# Entrenadorv01.net
KiCad netlist of a schematic drawn in EAGLE
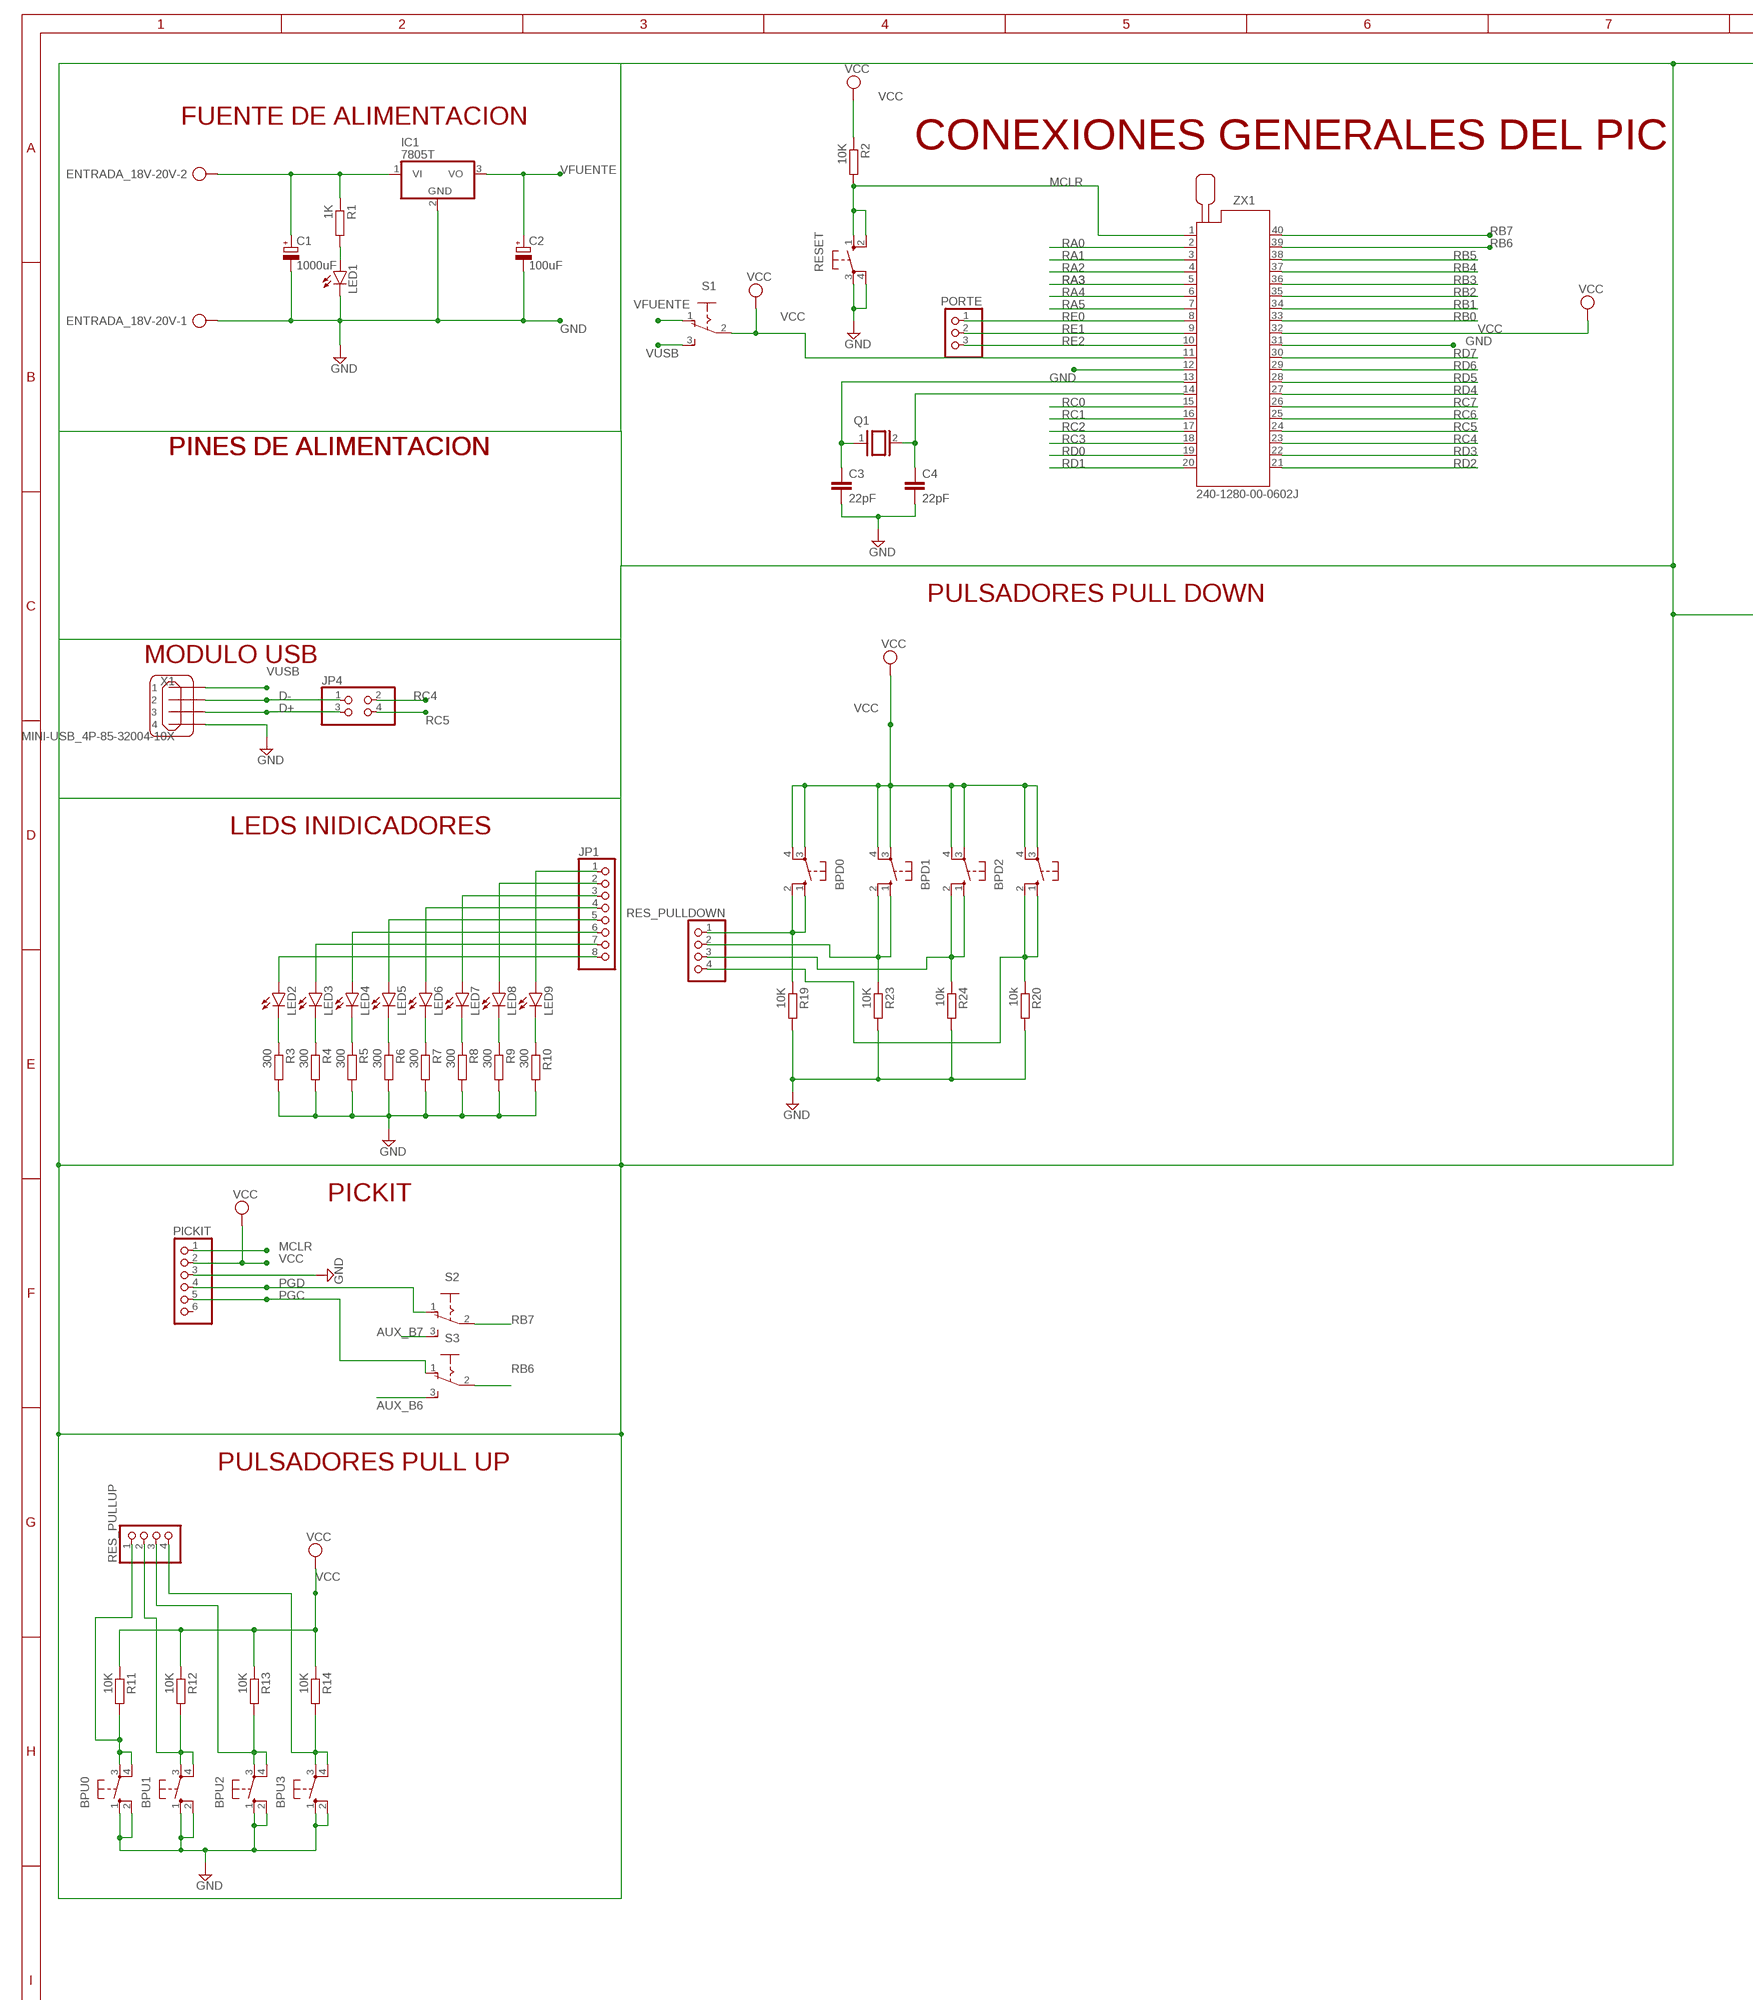
[diagram p0: schematic, sheet 1, part 1 of 2]
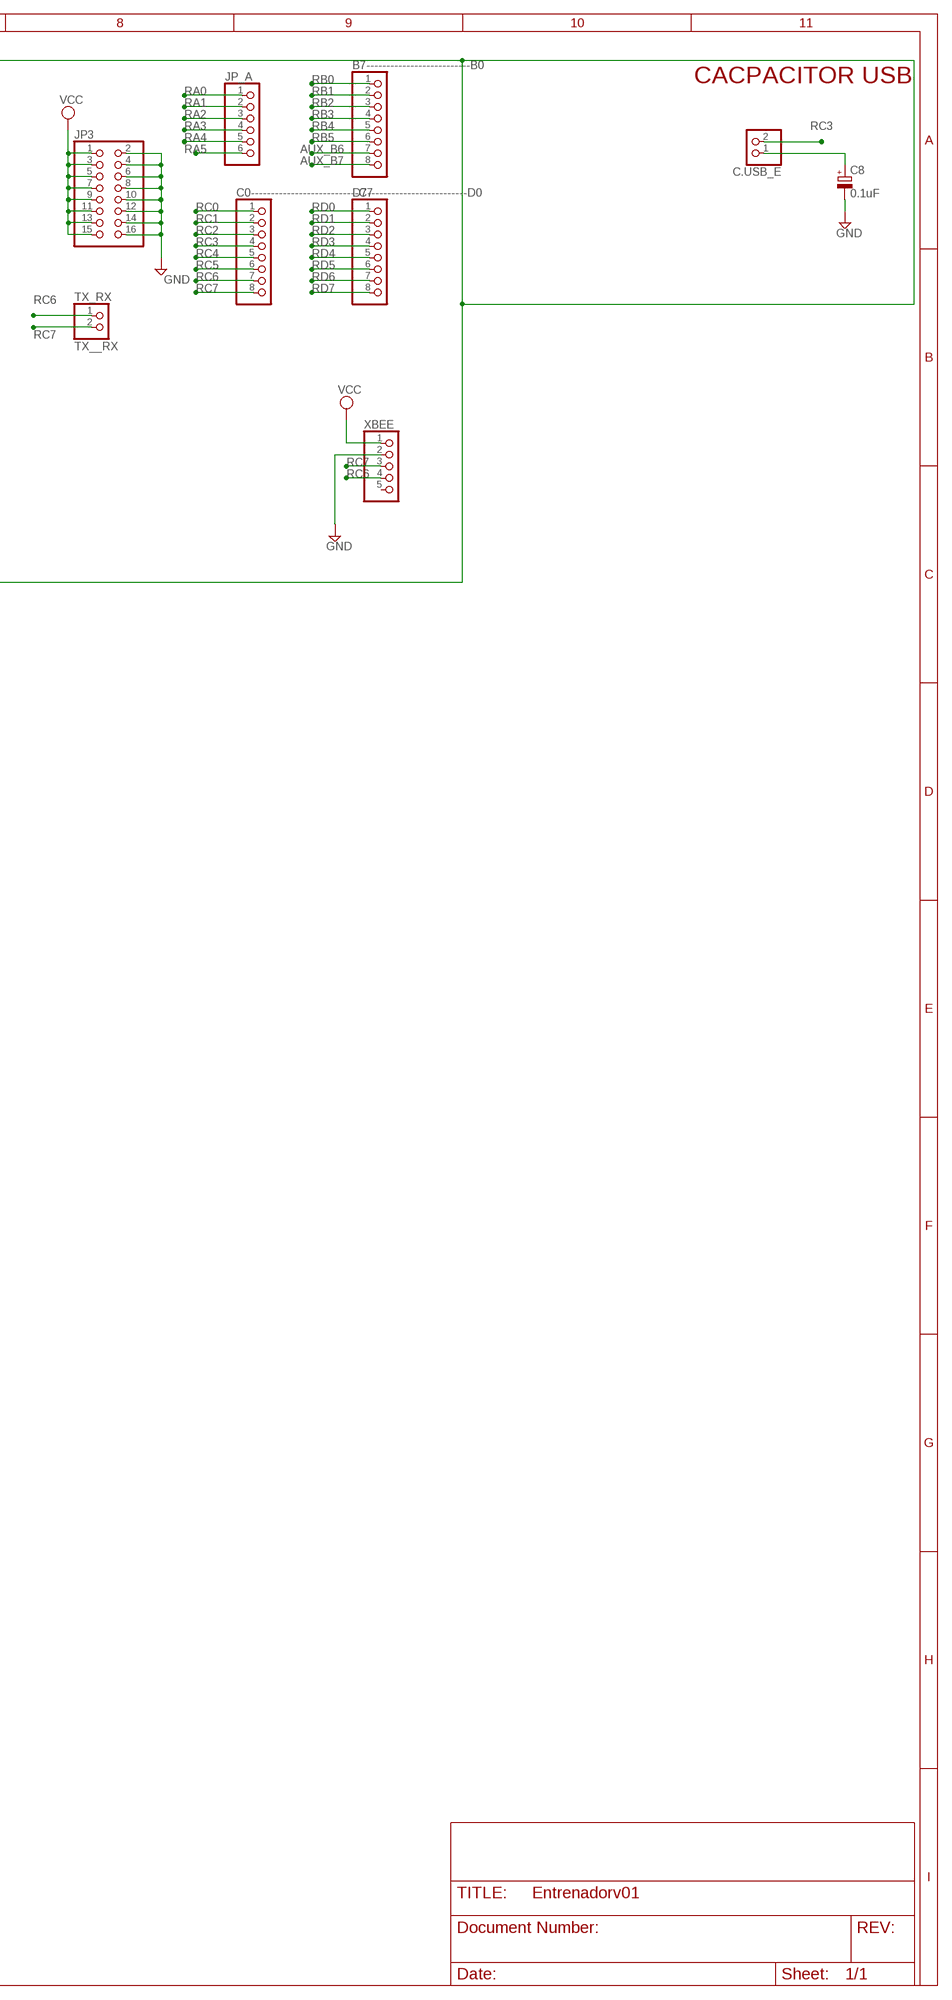
[diagram p1: schematic, sheet 1, part 2 of 2]

(export (version "E")
  (design (tool "Eeschema 10.0.6"))
  (components
    (comp (ref "B7--------------------------B0")
      (value "PINHD-1X8")
      (footprint "eagle-import:1X08")
      (libsource (lib "eagle-import") (part "PINHD-1X8"))
    )
    (comp (ref "BPD0")
      (value "10-XX")
      (footprint "eagle-import:B3F-10XX")
      (fields (field (name "MPN") "B3F-1000"))
      (libsource (lib "eagle-import") (part "10-XX"))
    )
    (comp (ref "BPD1")
      (value "10-XX")
      (footprint "eagle-import:B3F-10XX")
      (fields (field (name "MPN") "B3F-1000"))
      (libsource (lib "eagle-import") (part "10-XX"))
    )
    (comp (ref "BPD2")
      (value "10-XX")
      (footprint "eagle-import:B3F-10XX")
      (fields (field (name "MPN") "B3F-1000"))
      (libsource (lib "eagle-import") (part "10-XX"))
    )
    (comp (ref "BPD3")
      (value "10-XX")
      (footprint "eagle-import:B3F-10XX")
      (fields (field (name "MPN") "B3F-1000"))
      (libsource (lib "eagle-import") (part "10-XX"))
    )
    (comp (ref "BPU0")
      (value "10-XX")
      (footprint "eagle-import:B3F-10XX")
      (fields (field (name "MPN") "B3F-1000"))
      (libsource (lib "eagle-import") (part "10-XX"))
    )
    (comp (ref "BPU1")
      (value "10-XX")
      (footprint "eagle-import:B3F-10XX")
      (fields (field (name "MPN") "B3F-1000"))
      (libsource (lib "eagle-import") (part "10-XX"))
    )
    (comp (ref "BPU2")
      (value "10-XX")
      (footprint "eagle-import:B3F-10XX")
      (fields (field (name "MPN") "B3F-1000"))
      (libsource (lib "eagle-import") (part "10-XX"))
    )
    (comp (ref "BPU3")
      (value "10-XX")
      (footprint "eagle-import:B3F-10XX")
      (fields (field (name "MPN") "B3F-1000"))
      (libsource (lib "eagle-import") (part "10-XX"))
    )
    (comp (ref "C.USB_E")
      (value "PINHD-1X2")
      (footprint "eagle-import:1X02")
      (libsource (lib "eagle-import") (part "PINHD-1X2"))
    )
    (comp (ref "C0---------------------------C7")
      (value "PINHD-1X8")
      (footprint "eagle-import:1X08")
      (libsource (lib "eagle-import") (part "PINHD-1X8"))
    )
    (comp (ref "C1")
      (value "1000uF")
      (footprint "eagle-import:E5-10,5")
      (libsource (lib "eagle-import") (part "CPOL-EUE5-10.5"))
    )
    (comp (ref "C2")
      (value "100uF")
      (footprint "eagle-import:E5-10,5")
      (libsource (lib "eagle-import") (part "CPOL-EUE5-10.5"))
    )
    (comp (ref "C3")
      (value "22pF")
      (footprint "eagle-import:C025-025X050")
      (libsource (lib "eagle-import") (part "C-EU025-025X050"))
    )
    (comp (ref "C4")
      (value "22pF")
      (footprint "eagle-import:C025-025X050")
      (libsource (lib "eagle-import") (part "C-EU025-025X050"))
    )
    (comp (ref "C8")
      (value "0.1uF")
      (footprint "eagle-import:E1,8-4")
      (libsource (lib "eagle-import") (part "CPOL-EUE1.8-4"))
    )
    (comp (ref "D7-------------------------D0")
      (value "PINHD-1X8")
      (footprint "eagle-import:1X08")
      (libsource (lib "eagle-import") (part "PINHD-1X8"))
    )
    (comp (ref "ENTRADA_18V-20V")
      (value "AK300/2")
      (footprint "eagle-import:AK300_2")
      (libsource (lib "eagle-import") (part "AK300/2"))
    )
    (comp (ref "IC1")
      (value "7805T")
      (footprint "eagle-import:TO220H")
      (libsource (lib "eagle-import") (part "78T05"))
    )
    (comp (ref "JP1")
      (value "PINHD-1X8")
      (footprint "eagle-import:1X08")
      (libsource (lib "eagle-import") (part "PINHD-1X8"))
    )
    (comp (ref "JP3")
      (value "PINHD-2X8")
      (footprint "eagle-import:2X08")
      (libsource (lib "eagle-import") (part "PINHD-2X8"))
    )
    (comp (ref "JP4")
      (value "PINHD-2X2")
      (footprint "eagle-import:2X02")
      (libsource (lib "eagle-import") (part "PINHD-2X2"))
    )
    (comp (ref "JP_A")
      (value "PINHD-1X6")
      (footprint "eagle-import:1X06")
      (libsource (lib "eagle-import") (part "PINHD-1X6"))
    )
    (comp (ref "LED1")
      (value "LED3MM")
      (footprint "eagle-import:LED3MM")
      (libsource (lib "eagle-import") (part "LED3MM"))
    )
    (comp (ref "LED2")
      (value "LED3MM")
      (footprint "eagle-import:LED3MM")
      (libsource (lib "eagle-import") (part "LED3MM"))
    )
    (comp (ref "LED3")
      (value "LED3MM")
      (footprint "eagle-import:LED3MM")
      (libsource (lib "eagle-import") (part "LED3MM"))
    )
    (comp (ref "LED4")
      (value "LED3MM")
      (footprint "eagle-import:LED3MM")
      (libsource (lib "eagle-import") (part "LED3MM"))
    )
    (comp (ref "LED5")
      (value "LED3MM")
      (footprint "eagle-import:LED3MM")
      (libsource (lib "eagle-import") (part "LED3MM"))
    )
    (comp (ref "LED6")
      (value "LED3MM")
      (footprint "eagle-import:LED3MM")
      (libsource (lib "eagle-import") (part "LED3MM"))
    )
    (comp (ref "LED7")
      (value "LED3MM")
      (footprint "eagle-import:LED3MM")
      (libsource (lib "eagle-import") (part "LED3MM"))
    )
    (comp (ref "LED8")
      (value "LED3MM")
      (footprint "eagle-import:LED3MM")
      (libsource (lib "eagle-import") (part "LED3MM"))
    )
    (comp (ref "LED9")
      (value "LED3MM")
      (footprint "eagle-import:LED3MM")
      (libsource (lib "eagle-import") (part "LED3MM"))
    )
    (comp (ref "PICKIT")
      (value "PINHD-1X6")
      (footprint "eagle-import:1X06")
      (libsource (lib "eagle-import") (part "PINHD-1X6"))
    )
    (comp (ref "PORTE")
      (value "PINHD-1X3")
      (footprint "eagle-import:1X03")
      (libsource (lib "eagle-import") (part "PINHD-1X3"))
    )
    (comp (ref "Q1")
      (value "XTAL/S")
      (footprint "eagle-import:QS")
      (libsource (lib "eagle-import") (part "XTAL/S"))
    )
    (comp (ref "R1")
      (value "1K")
      (footprint "eagle-import:0207_10")
      (libsource (lib "eagle-import") (part "R-EU_0207/10"))
    )
    (comp (ref "R2")
      (value "10K")
      (footprint "eagle-import:0207_10")
      (libsource (lib "eagle-import") (part "R-EU_0207/10"))
    )
    (comp (ref "R3")
      (value "300")
      (footprint "eagle-import:0207_10")
      (libsource (lib "eagle-import") (part "R-EU_0207/10"))
    )
    (comp (ref "R4")
      (value "300")
      (footprint "eagle-import:0207_10")
      (libsource (lib "eagle-import") (part "R-EU_0207/10"))
    )
    (comp (ref "R5")
      (value "300")
      (footprint "eagle-import:0207_10")
      (libsource (lib "eagle-import") (part "R-EU_0207/10"))
    )
    (comp (ref "R6")
      (value "300")
      (footprint "eagle-import:0207_10")
      (libsource (lib "eagle-import") (part "R-EU_0207/10"))
    )
    (comp (ref "R7")
      (value "300")
      (footprint "eagle-import:0207_10")
      (libsource (lib "eagle-import") (part "R-EU_0207/10"))
    )
    (comp (ref "R8")
      (value "300")
      (footprint "eagle-import:0207_10")
      (libsource (lib "eagle-import") (part "R-EU_0207/10"))
    )
    (comp (ref "R9")
      (value "300")
      (footprint "eagle-import:0207_10")
      (libsource (lib "eagle-import") (part "R-EU_0207/10"))
    )
    (comp (ref "R10")
      (value "300")
      (footprint "eagle-import:0207_10")
      (libsource (lib "eagle-import") (part "R-EU_0207/10"))
    )
    (comp (ref "R11")
      (value "10K")
      (footprint "eagle-import:0207_10")
      (libsource (lib "eagle-import") (part "R-EU_0207/10"))
    )
    (comp (ref "R12")
      (value "10K")
      (footprint "eagle-import:0207_10")
      (libsource (lib "eagle-import") (part "R-EU_0207/10"))
    )
    (comp (ref "R13")
      (value "10K")
      (footprint "eagle-import:0207_10")
      (libsource (lib "eagle-import") (part "R-EU_0207/10"))
    )
    (comp (ref "R14")
      (value "10K")
      (footprint "eagle-import:0207_10")
      (libsource (lib "eagle-import") (part "R-EU_0207/10"))
    )
    (comp (ref "R19")
      (value "10K")
      (footprint "eagle-import:0207_10")
      (libsource (lib "eagle-import") (part "R-EU_0207/10"))
    )
    (comp (ref "R20")
      (value "10k")
      (footprint "eagle-import:0207_10")
      (libsource (lib "eagle-import") (part "R-EU_0207/10"))
    )
    (comp (ref "R23")
      (value "10K")
      (footprint "eagle-import:0207_10")
      (libsource (lib "eagle-import") (part "R-EU_0207/10"))
    )
    (comp (ref "R24")
      (value "10k")
      (footprint "eagle-import:0207_10")
      (libsource (lib "eagle-import") (part "R-EU_0207/10"))
    )
    (comp (ref "RESET")
      (value "10-XX")
      (footprint "eagle-import:B3F-10XX")
      (fields (field (name "MPN") "B3F-1000"))
      (libsource (lib "eagle-import") (part "10-XX"))
    )
    (comp (ref "RES_PULLDOWN")
      (value "PINHD-1X4")
      (footprint "eagle-import:1X04")
      (libsource (lib "eagle-import") (part "PINHD-1X4"))
    )
    (comp (ref "RES_PULLUP")
      (value "PINHD-1X4")
      (footprint "eagle-import:1X04")
      (libsource (lib "eagle-import") (part "PINHD-1X4"))
    )
    (comp (ref "S1")
      (value "M251")
      (footprint "eagle-import:M251")
      (libsource (lib "eagle-import") (part "M251"))
    )
    (comp (ref "S2")
      (value "M251")
      (footprint "eagle-import:M251")
      (libsource (lib "eagle-import") (part "M251"))
    )
    (comp (ref "S3")
      (value "M251")
      (footprint "eagle-import:M251")
      (libsource (lib "eagle-import") (part "M251"))
    )
    (comp (ref "TX_RX")
      (value "TX__RX")
      (footprint "eagle-import:1X02")
      (libsource (lib "eagle-import") (part "PINHD-1X2"))
    )
    (comp (ref "X1")
      (value "MINI-USB_4P-85-32004-10X")
      (footprint "eagle-import:85-32004-10X")
      (libsource (lib "eagle-import") (part "MINI-USB_4P-85-32004-10X"))
    )
    (comp (ref "XBEE")
      (value "PINHD-1X5")
      (footprint "eagle-import:1X05")
      (libsource (lib "eagle-import") (part "PINHD-1X5"))
    )
    (comp (ref "ZX1")
      (value "240-1280-00-0602J")
      (footprint "eagle-import:240-1280-00-0602J")
      (fields (field (name "MF") "3M"))
      (libsource (lib "eagle-import") (part "240-?-00-0602J1280"))
    )
  )
  (nets
    (net (code "1") (name "/AUX_B6") (class "Default")
      (node (ref "B7--------------------------B0") (pin "7") (pinfunction "7_7") (pintype "passive"))
      (node (ref "S3") (pin "3") (pinfunction "S_3") (pintype "passive"))
    )
    (net (code "2") (name "/AUX_B7") (class "Default")
      (node (ref "B7--------------------------B0") (pin "8") (pinfunction "8_8") (pintype "passive"))
      (node (ref "S2") (pin "3") (pinfunction "S_3") (pintype "passive"))
    )
    (net (code "3") (name "/D+") (class "Default")
      (node (ref "JP4") (pin "3") (pinfunction "3_3") (pintype "passive"))
      (node (ref "X1") (pin "3") (pinfunction "3_3") (pintype "passive"))
    )
    (net (code "4") (name "/D-") (class "Default")
      (node (ref "JP4") (pin "1") (pinfunction "1_1") (pintype "passive"))
      (node (ref "X1") (pin "2") (pinfunction "2_2") (pintype "passive"))
    )
    (net (code "5") (name "/MCLR") (class "Default")
      (node (ref "PICKIT") (pin "1") (pinfunction "1_1") (pintype "passive"))
      (node (ref "R2") (pin "2") (pinfunction "2_2") (pintype "passive"))
      (node (ref "RESET") (pin "1") (pinfunction "S_1") (pintype "passive"))
      (node (ref "RESET") (pin "2") (pinfunction "S1_2") (pintype "passive"))
      (node (ref "ZX1") (pin "1") (pinfunction "1_1") (pintype "passive"))
    )
    (net (code "6") (name "/PGC") (class "Default")
      (node (ref "PICKIT") (pin "5") (pinfunction "5_5") (pintype "passive"))
      (node (ref "S3") (pin "1") (pinfunction "O_1") (pintype "passive"))
    )
    (net (code "7") (name "/PGD") (class "Default")
      (node (ref "PICKIT") (pin "4") (pinfunction "4_4") (pintype "passive"))
      (node (ref "S2") (pin "1") (pinfunction "O_1") (pintype "passive"))
    )
    (net (code "8") (name "/RA0") (class "Default")
      (node (ref "JP_A") (pin "1") (pinfunction "1_1") (pintype "passive"))
      (node (ref "ZX1") (pin "2") (pinfunction "2_2") (pintype "passive"))
    )
    (net (code "9") (name "/RA1") (class "Default")
      (node (ref "JP_A") (pin "2") (pinfunction "2_2") (pintype "passive"))
      (node (ref "ZX1") (pin "3") (pinfunction "3_3") (pintype "passive"))
    )
    (net (code "10") (name "/RA2") (class "Default")
      (node (ref "JP_A") (pin "3") (pinfunction "3_3") (pintype "passive"))
      (node (ref "ZX1") (pin "4") (pinfunction "4_4") (pintype "passive"))
    )
    (net (code "11") (name "/RA3") (class "Default")
      (node (ref "JP_A") (pin "4") (pinfunction "4_4") (pintype "passive"))
      (node (ref "ZX1") (pin "5") (pinfunction "5_5") (pintype "passive"))
    )
    (net (code "12") (name "/RA4") (class "Default")
      (node (ref "JP_A") (pin "5") (pinfunction "5_5") (pintype "passive"))
      (node (ref "ZX1") (pin "6") (pinfunction "6_6") (pintype "passive"))
    )
    (net (code "13") (name "/RA5") (class "Default")
      (node (ref "JP_A") (pin "6") (pinfunction "6_6") (pintype "passive"))
      (node (ref "ZX1") (pin "7") (pinfunction "7_7") (pintype "passive"))
    )
    (net (code "14") (name "/RB0") (class "Default")
      (node (ref "B7--------------------------B0") (pin "1") (pinfunction "1_1") (pintype "passive"))
      (node (ref "ZX1") (pin "33") (pinfunction "33_33") (pintype "passive"))
    )
    (net (code "15") (name "/RB1") (class "Default")
      (node (ref "B7--------------------------B0") (pin "2") (pinfunction "2_2") (pintype "passive"))
      (node (ref "ZX1") (pin "34") (pinfunction "34_34") (pintype "passive"))
    )
    (net (code "16") (name "/RB2") (class "Default")
      (node (ref "B7--------------------------B0") (pin "3") (pinfunction "3_3") (pintype "passive"))
      (node (ref "ZX1") (pin "35") (pinfunction "35_35") (pintype "passive"))
    )
    (net (code "17") (name "/RB3") (class "Default")
      (node (ref "B7--------------------------B0") (pin "4") (pinfunction "4_4") (pintype "passive"))
      (node (ref "ZX1") (pin "36") (pinfunction "36_36") (pintype "passive"))
    )
    (net (code "18") (name "/RB4") (class "Default")
      (node (ref "B7--------------------------B0") (pin "5") (pinfunction "5_5") (pintype "passive"))
      (node (ref "ZX1") (pin "37") (pinfunction "37_37") (pintype "passive"))
    )
    (net (code "19") (name "/RB5") (class "Default")
      (node (ref "B7--------------------------B0") (pin "6") (pinfunction "6_6") (pintype "passive"))
      (node (ref "ZX1") (pin "38") (pinfunction "38_38") (pintype "passive"))
    )
    (net (code "20") (name "/RB6") (class "Default")
      (node (ref "S3") (pin "2") (pinfunction "P_2") (pintype "passive"))
      (node (ref "ZX1") (pin "39") (pinfunction "39_39") (pintype "passive"))
    )
    (net (code "21") (name "/RB7") (class "Default")
      (node (ref "S2") (pin "2") (pinfunction "P_2") (pintype "passive"))
      (node (ref "ZX1") (pin "40") (pinfunction "40_40") (pintype "passive"))
    )
    (net (code "22") (name "/RC0") (class "Default")
      (node (ref "C0---------------------------C7") (pin "1") (pinfunction "1_1") (pintype "passive"))
      (node (ref "ZX1") (pin "15") (pinfunction "15_15") (pintype "passive"))
    )
    (net (code "23") (name "/RC1") (class "Default")
      (node (ref "C0---------------------------C7") (pin "2") (pinfunction "2_2") (pintype "passive"))
      (node (ref "ZX1") (pin "16") (pinfunction "16_16") (pintype "passive"))
    )
    (net (code "24") (name "/RC2") (class "Default")
      (node (ref "C0---------------------------C7") (pin "3") (pinfunction "3_3") (pintype "passive"))
      (node (ref "ZX1") (pin "17") (pinfunction "17_17") (pintype "passive"))
    )
    (net (code "25") (name "/RC3") (class "Default")
      (node (ref "C.USB_E") (pin "2") (pinfunction "2_2") (pintype "passive"))
      (node (ref "C0---------------------------C7") (pin "4") (pinfunction "4_4") (pintype "passive"))
      (node (ref "ZX1") (pin "18") (pinfunction "18_18") (pintype "passive"))
    )
    (net (code "26") (name "/RC4") (class "Default")
      (node (ref "C0---------------------------C7") (pin "5") (pinfunction "5_5") (pintype "passive"))
      (node (ref "JP4") (pin "2") (pinfunction "2_2") (pintype "passive"))
      (node (ref "ZX1") (pin "23") (pinfunction "23_23") (pintype "passive"))
    )
    (net (code "27") (name "/RC5") (class "Default")
      (node (ref "C0---------------------------C7") (pin "6") (pinfunction "6_6") (pintype "passive"))
      (node (ref "JP4") (pin "4") (pinfunction "4_4") (pintype "passive"))
      (node (ref "ZX1") (pin "24") (pinfunction "24_24") (pintype "passive"))
    )
    (net (code "28") (name "/RC6") (class "Default")
      (node (ref "C0---------------------------C7") (pin "7") (pinfunction "7_7") (pintype "passive"))
      (node (ref "TX_RX") (pin "1") (pinfunction "1_1") (pintype "passive"))
      (node (ref "XBEE") (pin "4") (pinfunction "4_4") (pintype "passive"))
      (node (ref "ZX1") (pin "25") (pinfunction "25_25") (pintype "passive"))
    )
    (net (code "29") (name "/RC7") (class "Default")
      (node (ref "C0---------------------------C7") (pin "8") (pinfunction "8_8") (pintype "passive"))
      (node (ref "TX_RX") (pin "2") (pinfunction "2_2") (pintype "passive"))
      (node (ref "XBEE") (pin "3") (pinfunction "3_3") (pintype "passive"))
      (node (ref "ZX1") (pin "26") (pinfunction "26_26") (pintype "passive"))
    )
    (net (code "30") (name "/RD0") (class "Default")
      (node (ref "D7-------------------------D0") (pin "1") (pinfunction "1_1") (pintype "passive"))
      (node (ref "ZX1") (pin "19") (pinfunction "19_19") (pintype "passive"))
    )
    (net (code "31") (name "/RD1") (class "Default")
      (node (ref "D7-------------------------D0") (pin "2") (pinfunction "2_2") (pintype "passive"))
      (node (ref "ZX1") (pin "20") (pinfunction "20_20") (pintype "passive"))
    )
    (net (code "32") (name "/RD2") (class "Default")
      (node (ref "D7-------------------------D0") (pin "3") (pinfunction "3_3") (pintype "passive"))
      (node (ref "ZX1") (pin "21") (pinfunction "21_21") (pintype "passive"))
    )
    (net (code "33") (name "/RD3") (class "Default")
      (node (ref "D7-------------------------D0") (pin "4") (pinfunction "4_4") (pintype "passive"))
      (node (ref "ZX1") (pin "22") (pinfunction "22_22") (pintype "passive"))
    )
    (net (code "34") (name "/RD4") (class "Default")
      (node (ref "D7-------------------------D0") (pin "5") (pinfunction "5_5") (pintype "passive"))
      (node (ref "ZX1") (pin "27") (pinfunction "27_27") (pintype "passive"))
    )
    (net (code "35") (name "/RD5") (class "Default")
      (node (ref "D7-------------------------D0") (pin "6") (pinfunction "6_6") (pintype "passive"))
      (node (ref "ZX1") (pin "28") (pinfunction "28_28") (pintype "passive"))
    )
    (net (code "36") (name "/RD6") (class "Default")
      (node (ref "D7-------------------------D0") (pin "7") (pinfunction "7_7") (pintype "passive"))
      (node (ref "ZX1") (pin "29") (pinfunction "29_29") (pintype "passive"))
    )
    (net (code "37") (name "/RD7") (class "Default")
      (node (ref "D7-------------------------D0") (pin "8") (pinfunction "8_8") (pintype "passive"))
      (node (ref "ZX1") (pin "30") (pinfunction "30_30") (pintype "passive"))
    )
    (net (code "38") (name "/RE0") (class "Default")
      (node (ref "PORTE") (pin "1") (pinfunction "1_1") (pintype "passive"))
      (node (ref "ZX1") (pin "8") (pinfunction "8_8") (pintype "passive"))
    )
    (net (code "39") (name "/RE1") (class "Default")
      (node (ref "PORTE") (pin "2") (pinfunction "2_2") (pintype "passive"))
      (node (ref "ZX1") (pin "9") (pinfunction "9_9") (pintype "passive"))
    )
    (net (code "40") (name "/RE2") (class "Default")
      (node (ref "PORTE") (pin "3") (pinfunction "3_3") (pintype "passive"))
      (node (ref "ZX1") (pin "10") (pinfunction "10_10") (pintype "passive"))
    )
    (net (code "41") (name "/VFUENTE") (class "Default")
      (node (ref "C2") (pin "+") (pinfunction "+_+") (pintype "passive"))
      (node (ref "IC1") (pin "3") (pinfunction "VO_3") (pintype "passive"))
      (node (ref "S1") (pin "1") (pinfunction "O_1") (pintype "passive"))
    )
    (net (code "42") (name "/VUSB") (class "Default")
      (node (ref "S1") (pin "3") (pinfunction "S_3") (pintype "passive"))
      (node (ref "X1") (pin "1") (pinfunction "1_1") (pintype "passive"))
    )
    (net (code "43") (name "GND") (class "Default")
      (node (ref "BPU0") (pin "1") (pinfunction "S_1") (pintype "passive"))
      (node (ref "BPU0") (pin "2") (pinfunction "S1_2") (pintype "passive"))
      (node (ref "BPU1") (pin "1") (pinfunction "S_1") (pintype "passive"))
      (node (ref "BPU1") (pin "2") (pinfunction "S1_2") (pintype "passive"))
      (node (ref "BPU2") (pin "1") (pinfunction "S_1") (pintype "passive"))
      (node (ref "BPU2") (pin "2") (pinfunction "S1_2") (pintype "passive"))
      (node (ref "BPU3") (pin "1") (pinfunction "S_1") (pintype "passive"))
      (node (ref "BPU3") (pin "2") (pinfunction "S1_2") (pintype "passive"))
      (node (ref "C1") (pin "-") (pinfunction "-_-") (pintype "passive"))
      (node (ref "C2") (pin "-") (pinfunction "-_-") (pintype "passive"))
      (node (ref "C3") (pin "2") (pinfunction "2_2") (pintype "passive"))
      (node (ref "C4") (pin "2") (pinfunction "2_2") (pintype "passive"))
      (node (ref "C8") (pin "-") (pinfunction "-_-") (pintype "passive"))
      (node (ref "ENTRADA_18V-20V") (pin "1") (pinfunction "KL_1") (pintype "passive"))
      (node (ref "IC1") (pin "2") (pinfunction "GND_2") (pintype "passive"))
      (node (ref "JP3") (pin "10") (pinfunction "10_10") (pintype "passive"))
      (node (ref "JP3") (pin "12") (pinfunction "12_12") (pintype "passive"))
      (node (ref "JP3") (pin "14") (pinfunction "14_14") (pintype "passive"))
      (node (ref "JP3") (pin "16") (pinfunction "16_16") (pintype "passive"))
      (node (ref "JP3") (pin "2") (pinfunction "2_2") (pintype "passive"))
      (node (ref "JP3") (pin "4") (pinfunction "4_4") (pintype "passive"))
      (node (ref "JP3") (pin "6") (pinfunction "6_6") (pintype "passive"))
      (node (ref "JP3") (pin "8") (pinfunction "8_8") (pintype "passive"))
      (node (ref "LED1") (pin "K") (pinfunction "C_K") (pintype "passive"))
      (node (ref "PICKIT") (pin "3") (pinfunction "3_3") (pintype "passive"))
      (node (ref "R10") (pin "2") (pinfunction "2_2") (pintype "passive"))
      (node (ref "R19") (pin "2") (pinfunction "2_2") (pintype "passive"))
      (node (ref "R20") (pin "2") (pinfunction "2_2") (pintype "passive"))
      (node (ref "R23") (pin "2") (pinfunction "2_2") (pintype "passive"))
      (node (ref "R24") (pin "2") (pinfunction "2_2") (pintype "passive"))
      (node (ref "R3") (pin "2") (pinfunction "2_2") (pintype "passive"))
      (node (ref "R4") (pin "2") (pinfunction "2_2") (pintype "passive"))
      (node (ref "R5") (pin "2") (pinfunction "2_2") (pintype "passive"))
      (node (ref "R6") (pin "2") (pinfunction "2_2") (pintype "passive"))
      (node (ref "R7") (pin "2") (pinfunction "2_2") (pintype "passive"))
      (node (ref "R8") (pin "2") (pinfunction "2_2") (pintype "passive"))
      (node (ref "R9") (pin "2") (pinfunction "2_2") (pintype "passive"))
      (node (ref "RESET") (pin "3") (pinfunction "P_3") (pintype "passive"))
      (node (ref "RESET") (pin "4") (pinfunction "P1_4") (pintype "passive"))
      (node (ref "X1") (pin "4") (pinfunction "4_4") (pintype "passive"))
      (node (ref "XBEE") (pin "2") (pinfunction "2_2") (pintype "passive"))
      (node (ref "ZX1") (pin "12") (pinfunction "12_12") (pintype "passive"))
      (node (ref "ZX1") (pin "31") (pinfunction "31_31") (pintype "passive"))
    )
    (net (code "44") (name "Net-(BPD0-S)") (class "Default")
      (node (ref "BPD0") (pin "1") (pinfunction "S_1") (pintype "passive"))
      (node (ref "BPD0") (pin "2") (pinfunction "S1_2") (pintype "passive"))
      (node (ref "R19") (pin "1") (pinfunction "1_1") (pintype "passive"))
      (node (ref "RES_PULLDOWN") (pin "1") (pinfunction "1_1") (pintype "passive"))
    )
    (net (code "45") (name "Net-(BPD1-S)") (class "Default")
      (node (ref "BPD1") (pin "1") (pinfunction "S_1") (pintype "passive"))
      (node (ref "BPD1") (pin "2") (pinfunction "S1_2") (pintype "passive"))
      (node (ref "R23") (pin "1") (pinfunction "1_1") (pintype "passive"))
      (node (ref "RES_PULLDOWN") (pin "2") (pinfunction "2_2") (pintype "passive"))
    )
    (net (code "46") (name "Net-(BPD2-S)") (class "Default")
      (node (ref "BPD2") (pin "1") (pinfunction "S_1") (pintype "passive"))
      (node (ref "BPD2") (pin "2") (pinfunction "S1_2") (pintype "passive"))
      (node (ref "R24") (pin "1") (pinfunction "1_1") (pintype "passive"))
      (node (ref "RES_PULLDOWN") (pin "3") (pinfunction "3_3") (pintype "passive"))
    )
    (net (code "47") (name "Net-(BPD3-S)") (class "Default")
      (node (ref "BPD3") (pin "1") (pinfunction "S_1") (pintype "passive"))
      (node (ref "BPD3") (pin "2") (pinfunction "S1_2") (pintype "passive"))
      (node (ref "R20") (pin "1") (pinfunction "1_1") (pintype "passive"))
      (node (ref "RES_PULLDOWN") (pin "4") (pinfunction "4_4") (pintype "passive"))
    )
    (net (code "48") (name "Net-(BPU0-P)") (class "Default")
      (node (ref "BPU0") (pin "3") (pinfunction "P_3") (pintype "passive"))
      (node (ref "BPU0") (pin "4") (pinfunction "P1_4") (pintype "passive"))
      (node (ref "R11") (pin "2") (pinfunction "2_2") (pintype "passive"))
      (node (ref "RES_PULLUP") (pin "1") (pinfunction "1_1") (pintype "passive"))
    )
    (net (code "49") (name "Net-(BPU1-P)") (class "Default")
      (node (ref "BPU1") (pin "3") (pinfunction "P_3") (pintype "passive"))
      (node (ref "BPU1") (pin "4") (pinfunction "P1_4") (pintype "passive"))
      (node (ref "R12") (pin "2") (pinfunction "2_2") (pintype "passive"))
      (node (ref "RES_PULLUP") (pin "2") (pinfunction "2_2") (pintype "passive"))
    )
    (net (code "50") (name "Net-(BPU2-P)") (class "Default")
      (node (ref "BPU2") (pin "3") (pinfunction "P_3") (pintype "passive"))
      (node (ref "BPU2") (pin "4") (pinfunction "P1_4") (pintype "passive"))
      (node (ref "R13") (pin "2") (pinfunction "2_2") (pintype "passive"))
      (node (ref "RES_PULLUP") (pin "3") (pinfunction "3_3") (pintype "passive"))
    )
    (net (code "51") (name "Net-(BPU3-P)") (class "Default")
      (node (ref "BPU3") (pin "3") (pinfunction "P_3") (pintype "passive"))
      (node (ref "BPU3") (pin "4") (pinfunction "P1_4") (pintype "passive"))
      (node (ref "R14") (pin "2") (pinfunction "2_2") (pintype "passive"))
      (node (ref "RES_PULLUP") (pin "4") (pinfunction "4_4") (pintype "passive"))
    )
    (net (code "52") (name "Net-(C.USB_E-Pad1)") (class "Default")
      (node (ref "C.USB_E") (pin "1") (pinfunction "1_1") (pintype "passive"))
      (node (ref "C8") (pin "+") (pinfunction "+_+") (pintype "passive"))
    )
    (net (code "53") (name "Net-(C3-Pad1)") (class "Default")
      (node (ref "C3") (pin "1") (pinfunction "1_1") (pintype "passive"))
      (node (ref "Q1") (pin "1") (pinfunction "1_1") (pintype "passive"))
      (node (ref "ZX1") (pin "13") (pinfunction "13_13") (pintype "passive"))
    )
    (net (code "54") (name "Net-(C4-Pad1)") (class "Default")
      (node (ref "C4") (pin "1") (pinfunction "1_1") (pintype "passive"))
      (node (ref "Q1") (pin "2") (pinfunction "2_2") (pintype "passive"))
      (node (ref "ZX1") (pin "14") (pinfunction "14_14") (pintype "passive"))
    )
    (net (code "55") (name "Net-(ENTRADA_18V-20VB-KL)") (class "Default")
      (node (ref "C1") (pin "+") (pinfunction "+_+") (pintype "passive"))
      (node (ref "ENTRADA_18V-20V") (pin "2") (pinfunction "KL_2") (pintype "passive"))
      (node (ref "IC1") (pin "1") (pinfunction "VI_1") (pintype "input"))
      (node (ref "R1") (pin "1") (pinfunction "1_1") (pintype "passive"))
    )
    (net (code "56") (name "Net-(JP1-Pad1)") (class "Default")
      (node (ref "JP1") (pin "1") (pinfunction "1_1") (pintype "passive"))
      (node (ref "LED9") (pin "A") (pinfunction "A_A") (pintype "passive"))
    )
    (net (code "57") (name "Net-(JP1-Pad2)") (class "Default")
      (node (ref "JP1") (pin "2") (pinfunction "2_2") (pintype "passive"))
      (node (ref "LED8") (pin "A") (pinfunction "A_A") (pintype "passive"))
    )
    (net (code "58") (name "Net-(JP1-Pad3)") (class "Default")
      (node (ref "JP1") (pin "3") (pinfunction "3_3") (pintype "passive"))
      (node (ref "LED7") (pin "A") (pinfunction "A_A") (pintype "passive"))
    )
    (net (code "59") (name "Net-(JP1-Pad4)") (class "Default")
      (node (ref "JP1") (pin "4") (pinfunction "4_4") (pintype "passive"))
      (node (ref "LED6") (pin "A") (pinfunction "A_A") (pintype "passive"))
    )
    (net (code "60") (name "Net-(JP1-Pad5)") (class "Default")
      (node (ref "JP1") (pin "5") (pinfunction "5_5") (pintype "passive"))
      (node (ref "LED5") (pin "A") (pinfunction "A_A") (pintype "passive"))
    )
    (net (code "61") (name "Net-(JP1-Pad6)") (class "Default")
      (node (ref "JP1") (pin "6") (pinfunction "6_6") (pintype "passive"))
      (node (ref "LED4") (pin "A") (pinfunction "A_A") (pintype "passive"))
    )
    (net (code "62") (name "Net-(JP1-Pad7)") (class "Default")
      (node (ref "JP1") (pin "7") (pinfunction "7_7") (pintype "passive"))
      (node (ref "LED3") (pin "A") (pinfunction "A_A") (pintype "passive"))
    )
    (net (code "63") (name "Net-(JP1-Pad8)") (class "Default")
      (node (ref "JP1") (pin "8") (pinfunction "8_8") (pintype "passive"))
      (node (ref "LED2") (pin "A") (pinfunction "A_A") (pintype "passive"))
    )
    (net (code "64") (name "Net-(LED1-PadA)") (class "Default")
      (node (ref "LED1") (pin "A") (pinfunction "A_A") (pintype "passive"))
      (node (ref "R1") (pin "2") (pinfunction "2_2") (pintype "passive"))
    )
    (net (code "65") (name "Net-(LED2-C)") (class "Default")
      (node (ref "LED2") (pin "K") (pinfunction "C_K") (pintype "passive"))
      (node (ref "R3") (pin "1") (pinfunction "1_1") (pintype "passive"))
    )
    (net (code "66") (name "Net-(LED3-C)") (class "Default")
      (node (ref "LED3") (pin "K") (pinfunction "C_K") (pintype "passive"))
      (node (ref "R4") (pin "1") (pinfunction "1_1") (pintype "passive"))
    )
    (net (code "67") (name "Net-(LED4-C)") (class "Default")
      (node (ref "LED4") (pin "K") (pinfunction "C_K") (pintype "passive"))
      (node (ref "R5") (pin "1") (pinfunction "1_1") (pintype "passive"))
    )
    (net (code "68") (name "Net-(LED5-C)") (class "Default")
      (node (ref "LED5") (pin "K") (pinfunction "C_K") (pintype "passive"))
      (node (ref "R6") (pin "1") (pinfunction "1_1") (pintype "passive"))
    )
    (net (code "69") (name "Net-(LED6-C)") (class "Default")
      (node (ref "LED6") (pin "K") (pinfunction "C_K") (pintype "passive"))
      (node (ref "R7") (pin "1") (pinfunction "1_1") (pintype "passive"))
    )
    (net (code "70") (name "Net-(LED7-C)") (class "Default")
      (node (ref "LED7") (pin "K") (pinfunction "C_K") (pintype "passive"))
      (node (ref "R8") (pin "1") (pinfunction "1_1") (pintype "passive"))
    )
    (net (code "71") (name "Net-(LED8-C)") (class "Default")
      (node (ref "LED8") (pin "K") (pinfunction "C_K") (pintype "passive"))
      (node (ref "R9") (pin "1") (pinfunction "1_1") (pintype "passive"))
    )
    (net (code "72") (name "Net-(LED9-C)") (class "Default")
      (node (ref "LED9") (pin "K") (pinfunction "C_K") (pintype "passive"))
      (node (ref "R10") (pin "1") (pinfunction "1_1") (pintype "passive"))
    )
    (net (code "73") (name "VCC") (class "Default")
      (node (ref "BPD0") (pin "3") (pinfunction "P_3") (pintype "passive"))
      (node (ref "BPD0") (pin "4") (pinfunction "P1_4") (pintype "passive"))
      (node (ref "BPD1") (pin "3") (pinfunction "P_3") (pintype "passive"))
      (node (ref "BPD1") (pin "4") (pinfunction "P1_4") (pintype "passive"))
      (node (ref "BPD2") (pin "3") (pinfunction "P_3") (pintype "passive"))
      (node (ref "BPD2") (pin "4") (pinfunction "P1_4") (pintype "passive"))
      (node (ref "BPD3") (pin "3") (pinfunction "P_3") (pintype "passive"))
      (node (ref "BPD3") (pin "4") (pinfunction "P1_4") (pintype "passive"))
      (node (ref "JP3") (pin "1") (pinfunction "1_1") (pintype "passive"))
      (node (ref "JP3") (pin "11") (pinfunction "11_11") (pintype "passive"))
      (node (ref "JP3") (pin "13") (pinfunction "13_13") (pintype "passive"))
      (node (ref "JP3") (pin "15") (pinfunction "15_15") (pintype "passive"))
      (node (ref "JP3") (pin "3") (pinfunction "3_3") (pintype "passive"))
      (node (ref "JP3") (pin "5") (pinfunction "5_5") (pintype "passive"))
      (node (ref "JP3") (pin "7") (pinfunction "7_7") (pintype "passive"))
      (node (ref "JP3") (pin "9") (pinfunction "9_9") (pintype "passive"))
      (node (ref "PICKIT") (pin "2") (pinfunction "2_2") (pintype "passive"))
      (node (ref "R11") (pin "1") (pinfunction "1_1") (pintype "passive"))
      (node (ref "R12") (pin "1") (pinfunction "1_1") (pintype "passive"))
      (node (ref "R13") (pin "1") (pinfunction "1_1") (pintype "passive"))
      (node (ref "R14") (pin "1") (pinfunction "1_1") (pintype "passive"))
      (node (ref "R2") (pin "1") (pinfunction "1_1") (pintype "passive"))
      (node (ref "S1") (pin "2") (pinfunction "P_2") (pintype "passive"))
      (node (ref "XBEE") (pin "1") (pinfunction "1_1") (pintype "passive"))
      (node (ref "ZX1") (pin "11") (pinfunction "11_11") (pintype "passive"))
      (node (ref "ZX1") (pin "32") (pinfunction "32_32") (pintype "passive"))
    )
    (net (code "74") (name "unconnected-(PICKIT-Pad6)") (class "Default")
      (node (ref "PICKIT") (pin "6") (pinfunction "6_6") (pintype "passive"))
    )
    (net (code "75") (name "unconnected-(XBEE-Pad5)") (class "Default")
      (node (ref "XBEE") (pin "5") (pinfunction "5_5") (pintype "passive"))
    )
  )
)
